# XRACER-POWER-R07.net
KiCad netlist of a schematic drawn in Altium Designer
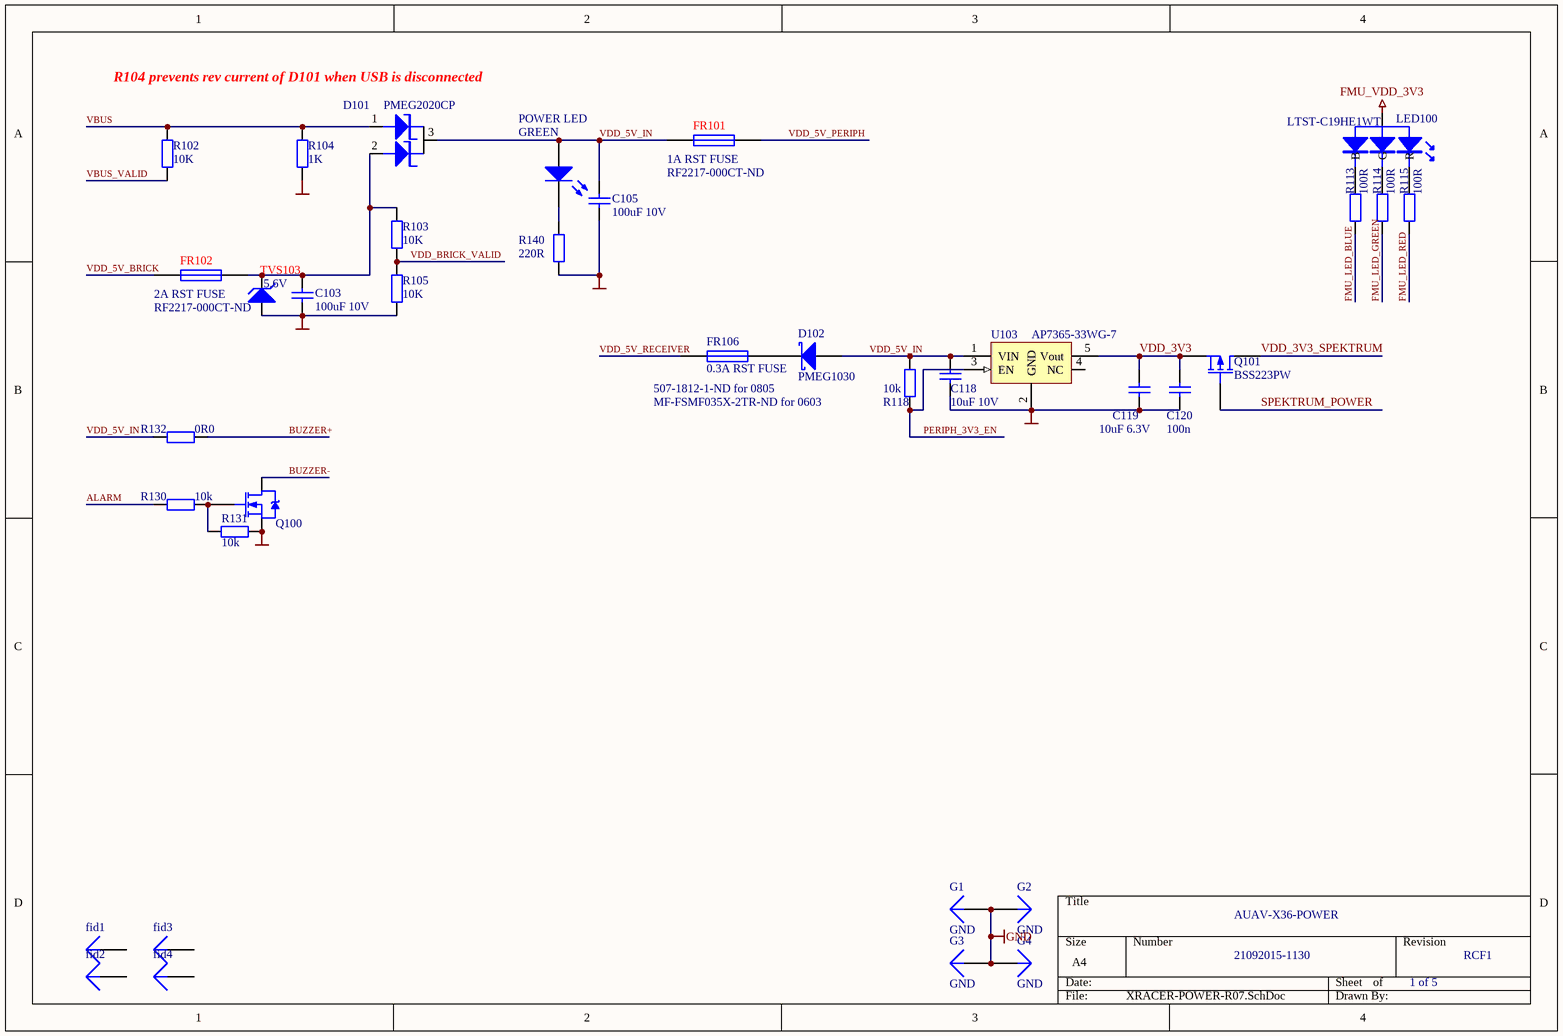
[diagram p0: XRACER-POWER-R07.SchDoc]

(export (version "E")
  (design (tool "Eeschema 10.0.6"))
  (components
    (comp (ref "C103")
      (value "100uF 10V")
      (footprint "0805A")
      (description "Capacitor")
      (fields (field (name "PUBLISHER") "Altium Limited"))
      (libsource (lib "Miscellaneous Devices") (part "Cap"))
    )
    (comp (ref "C105")
      (value "100uF 10V")
      (footprint "0805A")
      (description "Capacitor")
      (fields (field (name "PUBLISHER") "Altium Limited"))
      (libsource (lib "Miscellaneous Devices") (part "Cap"))
    )
    (comp (ref "C118")
      (value "10uF 10V")
      (footprint "0603A")
      (description "Capacitor")
      (fields (field (name "PUBLISHER") "Altium Limited"))
      (libsource (lib "Miscellaneous Devices") (part "Cap"))
    )
    (comp (ref "C119")
      (value "10uF 6.3V")
      (footprint "0603A")
      (description "Capacitor")
      (fields (field (name "PUBLISHER") "Altium Limited"))
      (libsource (lib "Miscellaneous Devices") (part "Cap"))
    )
    (comp (ref "C120")
      (value "100n")
      (footprint "0603A")
      (description "Capacitor")
      (fields (field (name "PUBLISHER") "Altium Limited"))
      (libsource (lib "Miscellaneous Devices") (part "Cap"))
    )
    (comp (ref "D101")
      (value "PMEG2020CP")
      (footprint "pmeg2020cp")
      (libsource (lib "My_Altium") (part "PMEG2020CP"))
    )
    (comp (ref "D102")
      (value "PMEG1030")
      (footprint "sod323f")
      (description "Schottky Diode")
      (fields (field (name "PUBLISHER") "Altium Limited"))
      (libsource (lib "Miscellaneous Devices") (part "D Schottky"))
    )
    (comp (ref "fid1")
      (value "~")
      (footprint "SMT_PAD")
      (description "Plug")
      (fields (field (name "PUBLISHER") "Altium Limited"))
      (libsource (lib "Miscellaneous Connectors") (part "Plug"))
    )
    (comp (ref "fid2")
      (value "~")
      (footprint "SMT_PAD")
      (description "Plug")
      (fields (field (name "PUBLISHER") "Altium Limited"))
      (libsource (lib "Miscellaneous Connectors") (part "Plug"))
    )
    (comp (ref "fid3")
      (value "~")
      (footprint "SMT_PAD")
      (description "Plug")
      (fields (field (name "PUBLISHER") "Altium Limited"))
      (libsource (lib "Miscellaneous Connectors") (part "Plug"))
    )
    (comp (ref "fid4")
      (value "~")
      (footprint "SMT_PAD")
      (description "Plug")
      (fields (field (name "PUBLISHER") "Altium Limited"))
      (libsource (lib "Miscellaneous Connectors") (part "Plug"))
    )
    (comp (ref "FR101")
      (value "1A RST FUSE")
      (footprint "0805A")
      (description "Fuse")
      (fields (field (name "DIGIKEY") "RF2217-000CT-ND") (field (name "PUBLISHER") "Altium Limited"))
      (libsource (lib "Miscellaneous Devices") (part "Fuse 1"))
    )
    (comp (ref "FR102")
      (value "2A RST FUSE")
      (footprint "0805A")
      (description "Fuse")
      (fields (field (name "DIGIKEY") "RF2217-000CT-ND") (field (name "PUBLISHER") "Altium Limited"))
      (libsource (lib "Miscellaneous Devices") (part "Fuse 1"))
    )
    (comp (ref "FR106")
      (value "0.3A RST FUSE")
      (footprint "0805A")
      (description "Fuse")
      (fields (field (name "PUBLISHER") "Altium Limited"))
      (libsource (lib "Miscellaneous Devices") (part "Fuse 1"))
    )
    (comp (ref "G1")
      (value "GND")
      (description "Plug")
      (fields (field (name "PUBLISHER") "Altium Limited"))
      (libsource (lib "Miscellaneous Connectors") (part "Plug"))
    )
    (comp (ref "G2")
      (value "GND")
      (description "Plug")
      (fields (field (name "PUBLISHER") "Altium Limited"))
      (libsource (lib "Miscellaneous Connectors") (part "Plug"))
    )
    (comp (ref "G3")
      (value "GND")
      (description "Plug")
      (fields (field (name "PUBLISHER") "Altium Limited"))
      (libsource (lib "Miscellaneous Connectors") (part "Plug"))
    )
    (comp (ref "G4")
      (value "GND")
      (description "Plug")
      (fields (field (name "PUBLISHER") "Altium Limited"))
      (libsource (lib "Miscellaneous Connectors") (part "Plug"))
    )
    (comp (ref "LED100")
      (value "LTST-C19HE1WT")
      (footprint "LTST-C19HE1WT")
      (libsource (lib "My_Altium") (part "RGB_LED_5MM"))
    )
    (comp (ref "POWER LED")
      (value "GREEN")
      (footprint "0603A")
      (description "Typical INFRARED GaAs LED")
      (fields (field (name "PUBLISHER") "Altium Limited"))
      (libsource (lib "Miscellaneous Devices") (part "LED0"))
    )
    (comp (ref "Q100")
      (value "DMG1012UW")
      (footprint "2N7002-SOT323")
      (description "N-Channel Power MOSFET")
      (fields (field (name "PUBLISHER") "Altium Limited"))
      (libsource (lib "Miscellaneous Devices") (part "NMOS-2"))
    )
    (comp (ref "Q101")
      (value "BSS223PW")
      (footprint "2N7002-SOT323")
      (description "P-Channel MOSFET")
      (fields (field (name "PUBLISHER") "Altium Limited"))
      (libsource (lib "Miscellaneous Devices") (part "MOSFET-P"))
    )
    (comp (ref "R102")
      (value "10K")
      (footprint "0603A")
      (description "Resistor")
      (fields (field (name "PUBLISHER") "Altium Limited"))
      (libsource (lib "") (part "Res2_1"))
    )
    (comp (ref "R103")
      (value "10K")
      (footprint "0603A")
      (description "Resistor")
      (fields (field (name "PUBLISHER") "Altium Limited"))
      (libsource (lib "Miscellaneous Devices") (part "Res2"))
    )
    (comp (ref "R104")
      (value "1K")
      (footprint "0603A")
      (description "Resistor")
      (fields (field (name "PUBLISHER") "Altium Limited"))
      (libsource (lib "") (part "Res2_1"))
    )
    (comp (ref "R105")
      (value "10K")
      (footprint "0603A")
      (description "Resistor")
      (fields (field (name "PUBLISHER") "Altium Limited"))
      (libsource (lib "Miscellaneous Devices") (part "Res2"))
    )
    (comp (ref "R113")
      (value "100R")
      (footprint "0402A")
      (description "Resistor")
      (fields (field (name "PUBLISHER") "Altium Limited"))
      (libsource (lib "") (part "Res2_1"))
    )
    (comp (ref "R114")
      (value "100R")
      (footprint "0402A")
      (description "Resistor")
      (fields (field (name "PUBLISHER") "Altium Limited"))
      (libsource (lib "") (part "Res2_1"))
    )
    (comp (ref "R115")
      (value "100R")
      (footprint "0402A")
      (description "Resistor")
      (fields (field (name "PUBLISHER") "Altium Limited"))
      (libsource (lib "") (part "Res2_1"))
    )
    (comp (ref "R118")
      (value "10k")
      (footprint "0603A")
      (description "Resistor")
      (fields (field (name "PUBLISHER") "Altium Limited"))
      (libsource (lib "") (part "Res2_1"))
    )
    (comp (ref "R130")
      (value "10k")
      (footprint "0402A")
      (description "Resistor")
      (fields (field (name "PUBLISHER") "Altium Limited"))
      (libsource (lib "") (part "Res2_2"))
    )
    (comp (ref "R131")
      (value "10k")
      (footprint "0402A")
      (description "Resistor")
      (fields (field (name "PUBLISHER") "Altium Limited"))
      (libsource (lib "") (part "Res2_3"))
    )
    (comp (ref "R132")
      (value "0R0")
      (footprint "0402A")
      (description "Resistor")
      (fields (field (name "PUBLISHER") "Altium Limited"))
      (libsource (lib "") (part "Res2_2"))
    )
    (comp (ref "R140")
      (value "220R")
      (footprint "0603A")
      (description "Resistor")
      (fields (field (name "PUBLISHER") "Altium Limited"))
      (libsource (lib "") (part "Res2_1"))
    )
    (comp (ref "TVS103")
      (value "5.6V")
      (footprint "SOD323F")
      (description "Zener Diode")
      (fields (field (name "PUBLISHER") "Altium Limited"))
      (libsource (lib "Miscellaneous Devices") (part "D Zener"))
    )
    (comp (ref "U103")
      (value "AP7365-33WG-7")
      (footprint "SOT23-5")
      (libsource (lib "My_Altium") (part "LP5907-Q1"))
    )
  )
  (nets
    (net (code "1") (name "/ALARM") (class "Default")
      (node (ref "R130") (pin "2") (pinfunction "2_2") (pintype "passive"))
    )
    (net (code "2") (name "/BUZZER+") (class "Default")
      (node (ref "R132") (pin "1") (pinfunction "1_1") (pintype "passive"))
    )
    (net (code "3") (name "/BUZZER-") (class "Default")
      (node (ref "Q100") (pin "1") (pinfunction "D_1") (pintype "passive"))
    )
    (net (code "4") (name "/FMU_LED_BLUE") (class "Default")
      (node (ref "R113") (pin "1") (pinfunction "1_1") (pintype "passive"))
    )
    (net (code "5") (name "/FMU_LED_GREEN") (class "Default")
      (node (ref "R114") (pin "1") (pinfunction "1_1") (pintype "passive"))
    )
    (net (code "6") (name "/FMU_LED_RED") (class "Default")
      (node (ref "R115") (pin "1") (pinfunction "1_1") (pintype "passive"))
    )
    (net (code "7") (name "/PERIPH_3V3_EN") (class "Default")
      (node (ref "R118") (pin "1") (pinfunction "1_1") (pintype "passive"))
      (node (ref "U103") (pin "3") (pinfunction "EN_3") (pintype "input"))
    )
    (net (code "8") (name "/SPEKTRUM_POWER") (class "Default")
      (node (ref "Q101") (pin "3") (pinfunction "G_3") (pintype "passive"))
    )
    (net (code "9") (name "/VBUS") (class "Default")
      (node (ref "D101") (pin "1") (pintype "passive"))
      (node (ref "R102") (pin "2") (pinfunction "2_2") (pintype "passive"))
      (node (ref "R104") (pin "2") (pinfunction "2_2") (pintype "passive"))
    )
    (net (code "10") (name "/VBUS_VALID") (class "Default")
      (node (ref "R102") (pin "1") (pinfunction "1_1") (pintype "passive"))
    )
    (net (code "11") (name "/VDD_3V3") (class "Default")
      (node (ref "C119") (pin "2") (pinfunction "2_2") (pintype "passive"))
      (node (ref "C120") (pin "2") (pinfunction "2_2") (pintype "passive"))
      (node (ref "Q101") (pin "2") (pinfunction "S_2") (pintype "passive"))
      (node (ref "U103") (pin "5") (pinfunction "Vout_5") (pintype "power_in"))
    )
    (net (code "12") (name "/VDD_3V3_SPEKTRUM") (class "Default")
      (node (ref "Q101") (pin "1") (pinfunction "D_1") (pintype "passive"))
    )
    (net (code "13") (name "/VDD_5V_BRICK") (class "Default")
      (node (ref "FR102") (pin "1") (pinfunction "1_1") (pintype "passive"))
    )
    (net (code "14") (name "/VDD_5V_IN") (class "Default")
      (node (ref "C105") (pin "2") (pinfunction "2_2") (pintype "passive"))
      (node (ref "C118") (pin "2") (pinfunction "2_2") (pintype "passive"))
      (node (ref "D101") (pin "3") (pintype "passive"))
      (node (ref "D102") (pin "1") (pinfunction "A_1") (pintype "passive"))
      (node (ref "FR101") (pin "1") (pinfunction "1_1") (pintype "passive"))
      (node (ref "POWER LED") (pin "1") (pinfunction "A_1") (pintype "passive"))
      (node (ref "R118") (pin "2") (pinfunction "2_2") (pintype "passive"))
      (node (ref "R132") (pin "2") (pinfunction "2_2") (pintype "passive"))
      (node (ref "U103") (pin "1") (pinfunction "VIN_1") (pintype "power_in"))
    )
    (net (code "15") (name "/VDD_5V_PERIPH") (class "Default")
      (node (ref "FR101") (pin "2") (pinfunction "2_2") (pintype "passive"))
    )
    (net (code "16") (name "/VDD_5V_RECEIVER") (class "Default")
      (node (ref "FR106") (pin "2") (pinfunction "2_2") (pintype "passive"))
    )
    (net (code "17") (name "/VDD_BRICK_VALID") (class "Default")
      (node (ref "R103") (pin "2") (pinfunction "2_2") (pintype "passive"))
      (node (ref "R105") (pin "1") (pinfunction "1_1") (pintype "passive"))
    )
    (net (code "18") (name "FMU_VDD_3V3") (class "Default")
      (node (ref "LED100") (pin "4") (pinfunction "A_4") (pintype "passive"))
    )
    (net (code "19") (name "GND") (class "Default")
      (node (ref "C103") (pin "1") (pinfunction "1_1") (pintype "passive"))
      (node (ref "C105") (pin "1") (pinfunction "1_1") (pintype "passive"))
      (node (ref "C118") (pin "1") (pinfunction "1_1") (pintype "passive"))
      (node (ref "C119") (pin "1") (pinfunction "1_1") (pintype "passive"))
      (node (ref "C120") (pin "1") (pinfunction "1_1") (pintype "passive"))
      (node (ref "G1") (pin "1") (pinfunction "1_1") (pintype "passive"))
      (node (ref "G2") (pin "1") (pinfunction "1_1") (pintype "passive"))
      (node (ref "G3") (pin "1") (pinfunction "1_1") (pintype "passive"))
      (node (ref "G4") (pin "1") (pinfunction "1_1") (pintype "passive"))
      (node (ref "Q100") (pin "2") (pinfunction "S_2") (pintype "passive"))
      (node (ref "R104") (pin "1") (pinfunction "1_1") (pintype "passive"))
      (node (ref "R105") (pin "2") (pinfunction "2_2") (pintype "passive"))
      (node (ref "R131") (pin "2") (pinfunction "2_2") (pintype "passive"))
      (node (ref "R140") (pin "1") (pinfunction "1_1") (pintype "passive"))
      (node (ref "TVS103") (pin "1") (pinfunction "A_1") (pintype "passive"))
      (node (ref "U103") (pin "2") (pinfunction "GND_2") (pintype "power_in"))
    )
    (net (code "20") (name "Net-(D102-K)") (class "Default")
      (node (ref "D102") (pin "2") (pinfunction "K_2") (pintype "passive"))
      (node (ref "FR106") (pin "1") (pinfunction "1_1") (pintype "passive"))
    )
    (net (code "21") (name "Net-(LED100-B)") (class "Default")
      (node (ref "LED100") (pin "3") (pinfunction "B_3") (pintype "passive"))
      (node (ref "R113") (pin "2") (pinfunction "2_2") (pintype "passive"))
    )
    (net (code "22") (name "Net-(LED100-G)") (class "Default")
      (node (ref "LED100") (pin "2") (pinfunction "G_2") (pintype "passive"))
      (node (ref "R114") (pin "2") (pinfunction "2_2") (pintype "passive"))
    )
    (net (code "23") (name "Net-(LED100-R)") (class "Default")
      (node (ref "LED100") (pin "1") (pinfunction "R_1") (pintype "passive"))
      (node (ref "R115") (pin "2") (pinfunction "2_2") (pintype "passive"))
    )
    (net (code "24") (name "Net-(POWER LED-K)") (class "Default")
      (node (ref "POWER LED") (pin "2") (pinfunction "K_2") (pintype "passive"))
      (node (ref "R140") (pin "2") (pinfunction "2_2") (pintype "passive"))
    )
    (net (code "25") (name "Net-(Q100-G)") (class "Default")
      (node (ref "Q100") (pin "3") (pinfunction "G_3") (pintype "passive"))
      (node (ref "R130") (pin "1") (pinfunction "1_1") (pintype "passive"))
      (node (ref "R131") (pin "1") (pinfunction "1_1") (pintype "passive"))
    )
    (net (code "26") (name "Net-(TVS103-K)") (class "Default")
      (node (ref "C103") (pin "2") (pinfunction "2_2") (pintype "passive"))
      (node (ref "D101") (pin "2") (pintype "passive"))
      (node (ref "FR102") (pin "2") (pinfunction "2_2") (pintype "passive"))
      (node (ref "R103") (pin "1") (pinfunction "1_1") (pintype "passive"))
      (node (ref "TVS103") (pin "2") (pinfunction "K_2") (pintype "passive"))
    )
    (net (code "27") (name "unconnected-(U103-NC-Pad4)") (class "Default")
      (node (ref "U103") (pin "4") (pinfunction "NC_4") (pintype "passive"))
    )
    (net (code "28") (name "unconnected-(fid1-Pad1)") (class "Default")
      (node (ref "fid1") (pin "1") (pinfunction "1_1") (pintype "passive"))
    )
    (net (code "29") (name "unconnected-(fid2-Pad1)") (class "Default")
      (node (ref "fid2") (pin "1") (pinfunction "1_1") (pintype "passive"))
    )
    (net (code "30") (name "unconnected-(fid3-Pad1)") (class "Default")
      (node (ref "fid3") (pin "1") (pinfunction "1_1") (pintype "passive"))
    )
    (net (code "31") (name "unconnected-(fid4-Pad1)") (class "Default")
      (node (ref "fid4") (pin "1") (pinfunction "1_1") (pintype "passive"))
    )
  )
)
